# integratedBertha.net
KiCad netlist of a schematic drawn in EAGLE
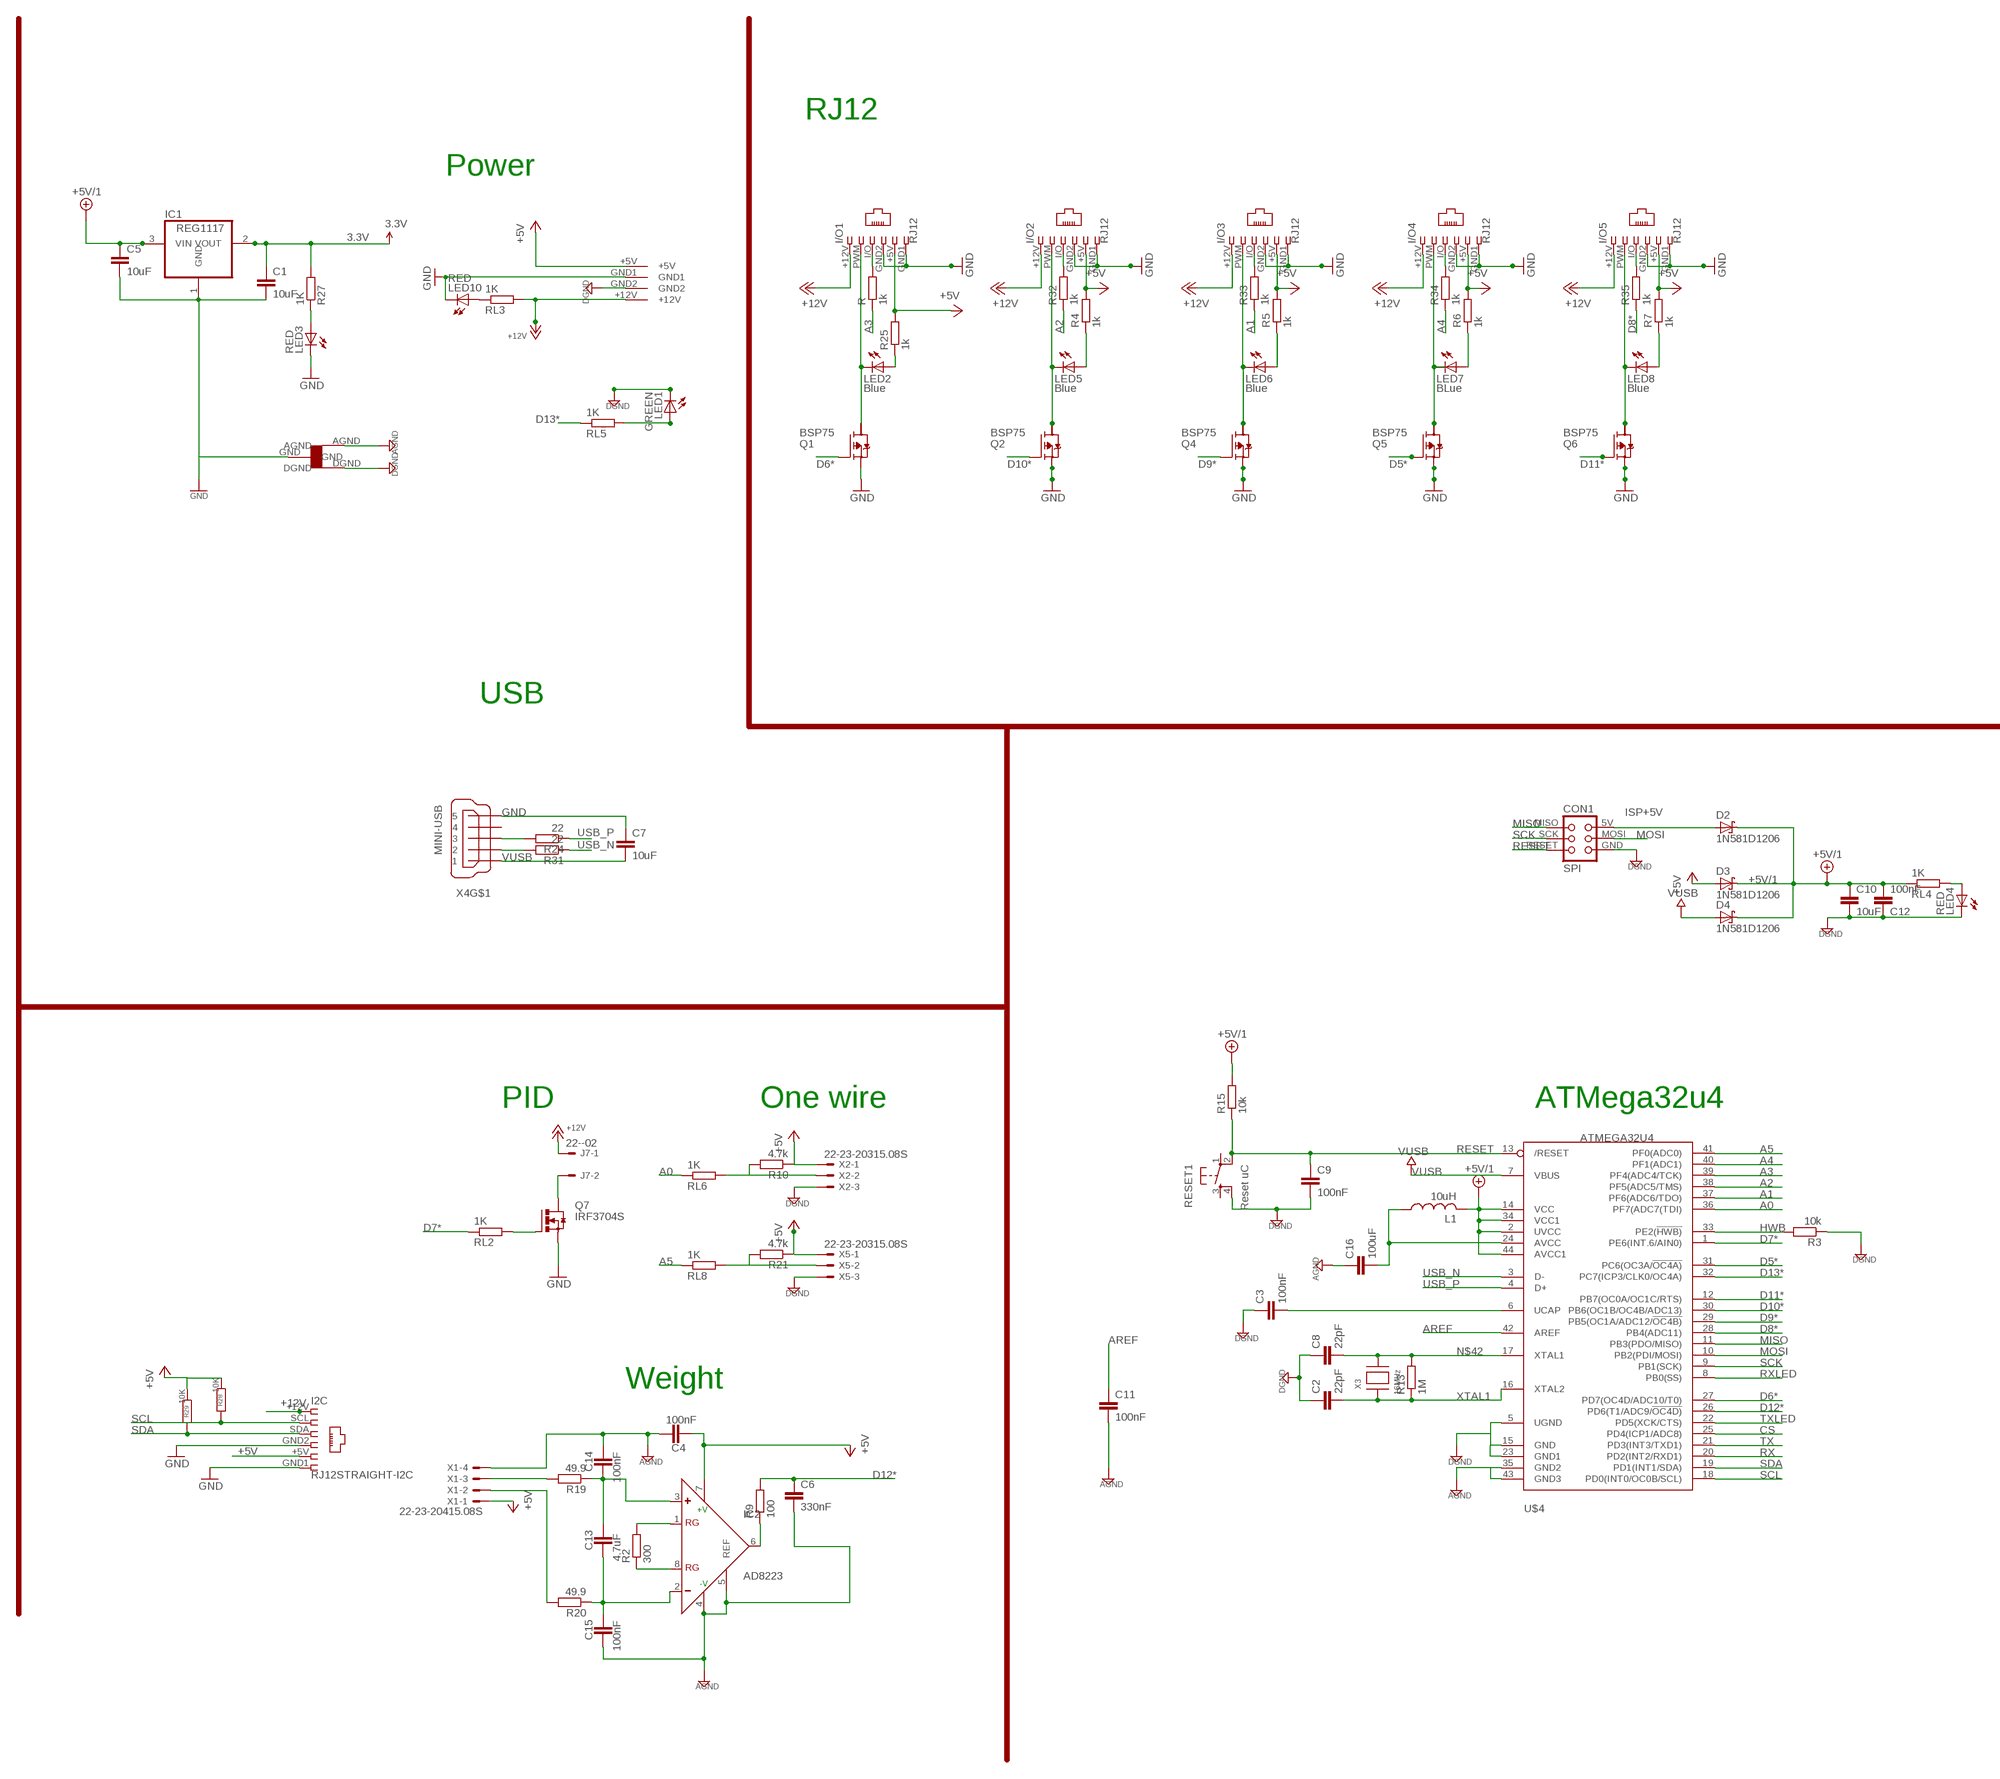
[diagram p0: schematic, sheet 1, part 1 of 2]
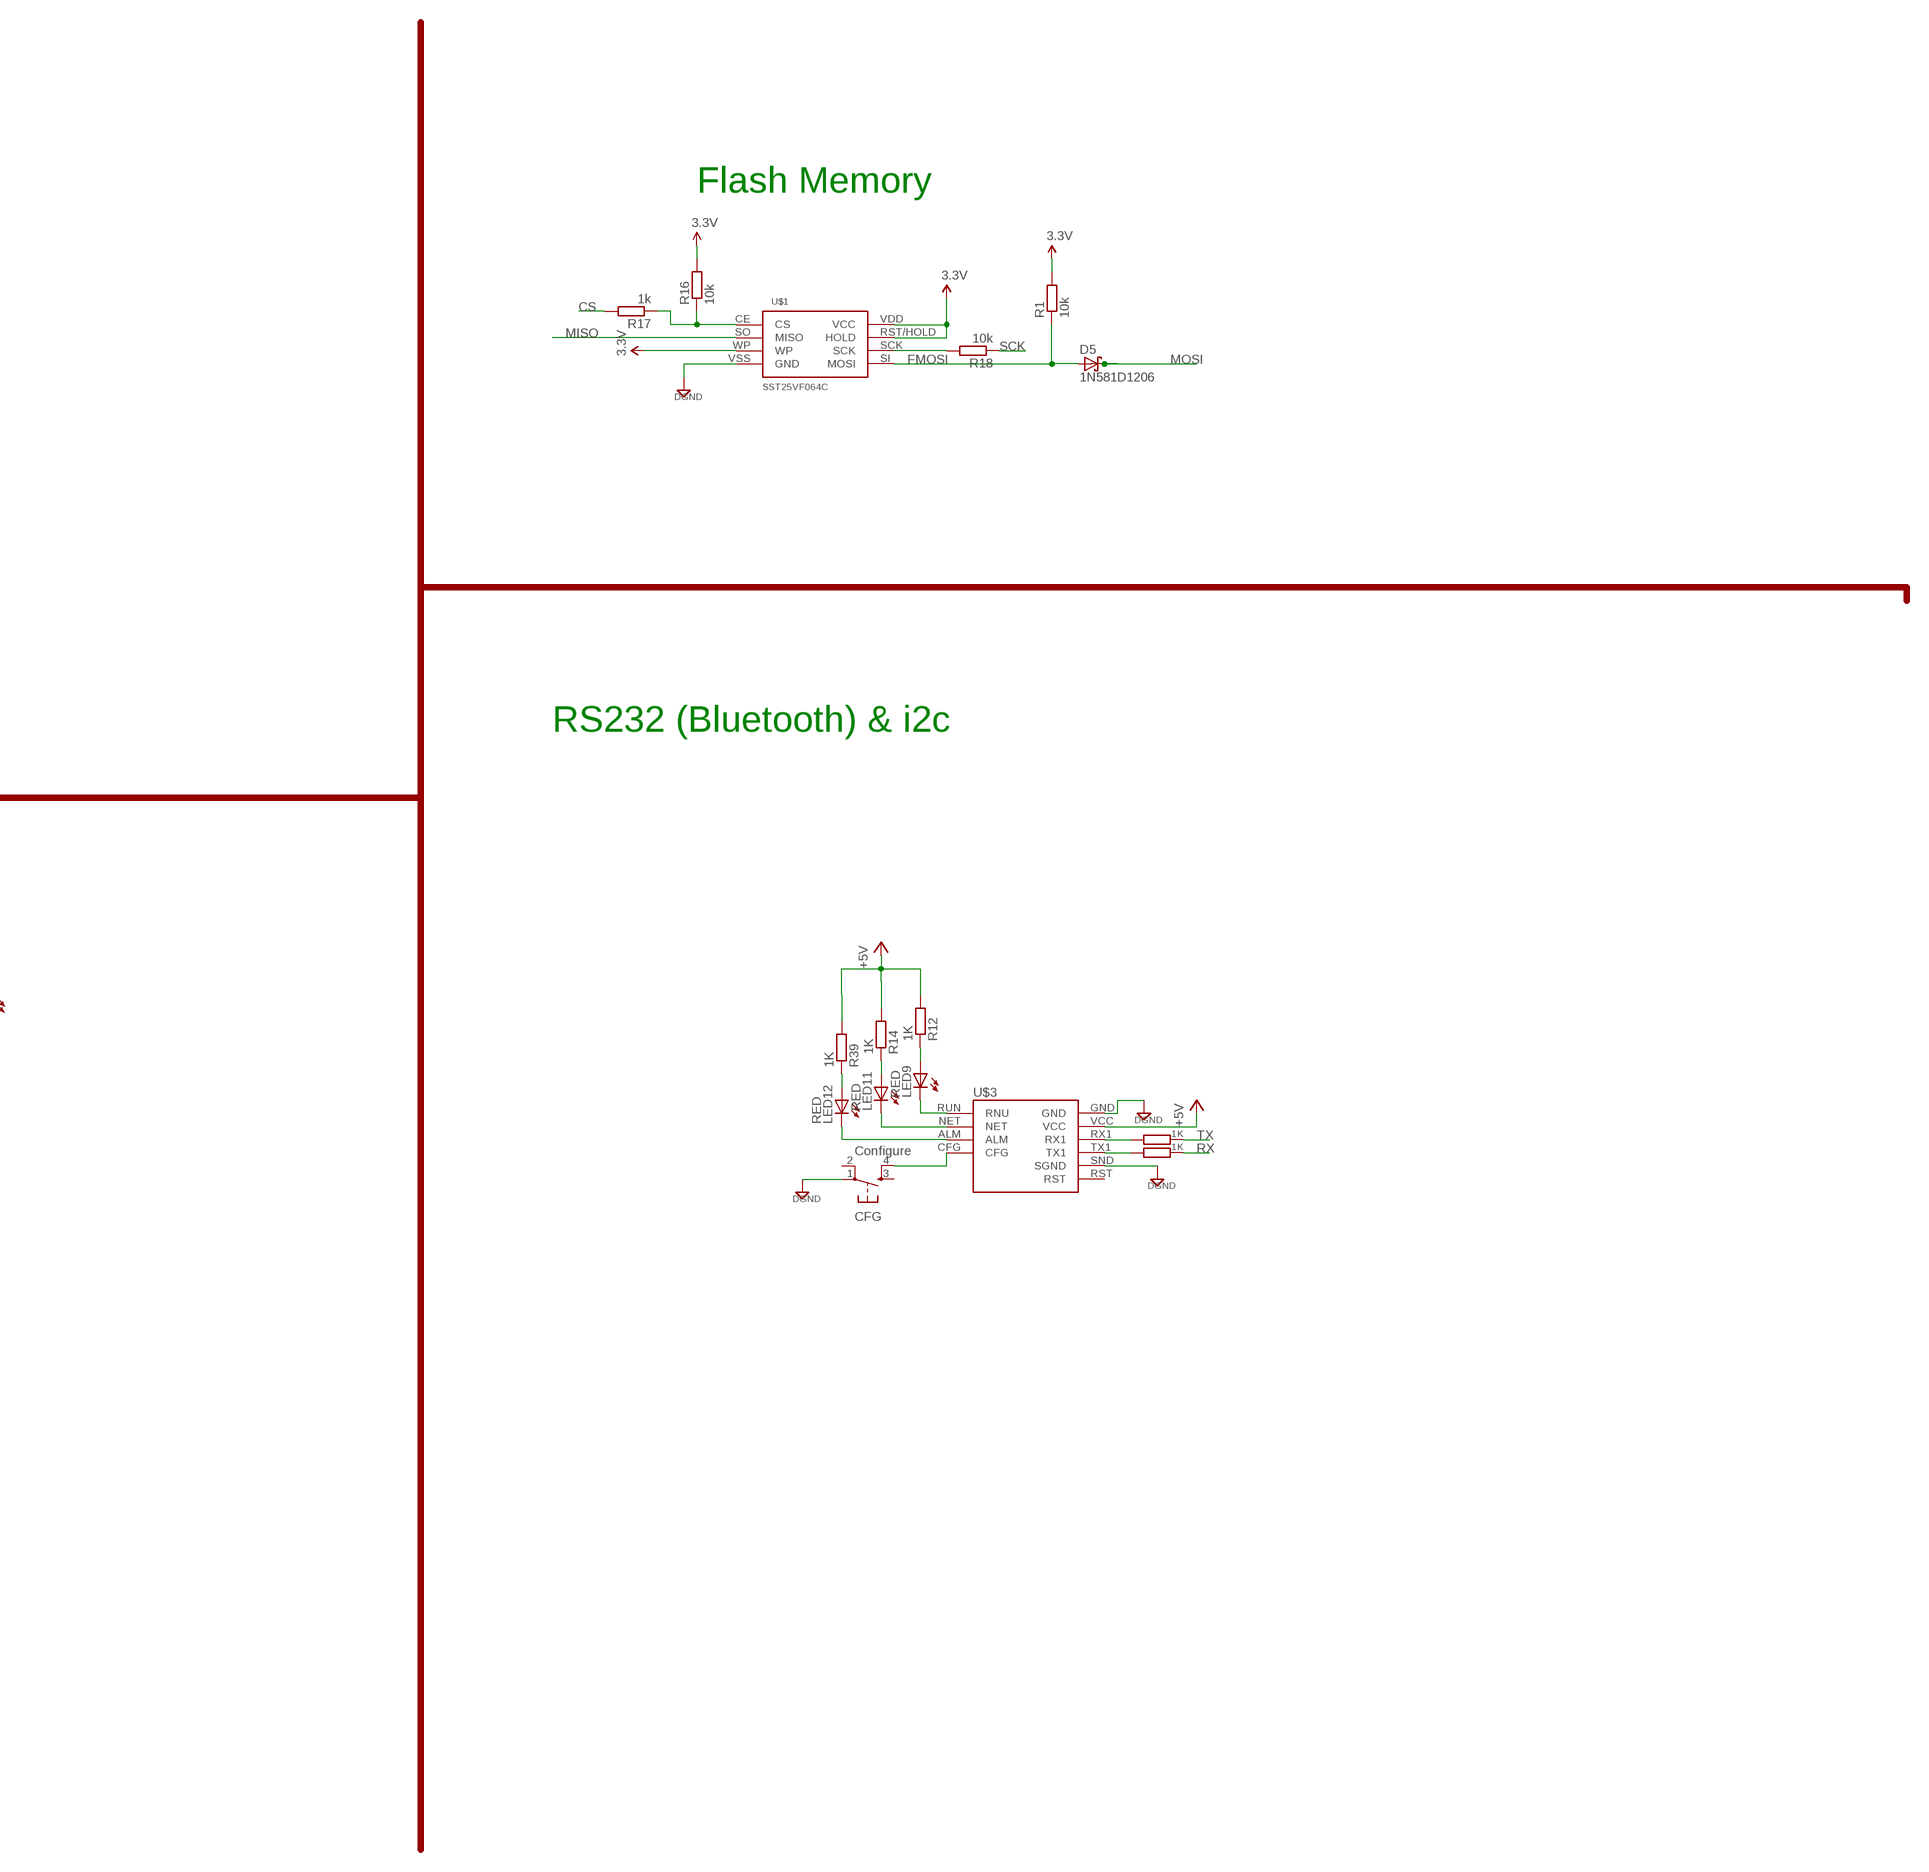
[diagram p1: schematic, sheet 1, part 2 of 2]

(export (version "E")
  (design (tool "Eeschema 10.0.6"))
  (components
    (comp (ref "C1")
      (value "10uF")
      (footprint "eagle-import:C1206")
      (libsource (lib "eagle-import") (part "C-EUC1206"))
    )
    (comp (ref "C2")
      (value "22pF")
      (footprint "eagle-import:C1206")
      (libsource (lib "eagle-import") (part "C-EUC1206"))
    )
    (comp (ref "C3")
      (value "100nF")
      (footprint "eagle-import:C1206")
      (libsource (lib "eagle-import") (part "C-EUC1206"))
    )
    (comp (ref "C4")
      (value "100nF")
      (footprint "eagle-import:C1206")
      (libsource (lib "eagle-import") (part "C-EUC1206"))
    )
    (comp (ref "C5")
      (value "10uF")
      (footprint "eagle-import:C1206")
      (libsource (lib "eagle-import") (part "C-EUC1206"))
    )
    (comp (ref "C6")
      (value "330nF")
      (footprint "eagle-import:C1206")
      (libsource (lib "eagle-import") (part "C-EUC1206"))
    )
    (comp (ref "C7")
      (value "10uF")
      (footprint "eagle-import:C1206")
      (libsource (lib "eagle-import") (part "C-EUC1206"))
    )
    (comp (ref "C8")
      (value "22pF")
      (footprint "eagle-import:C1206")
      (libsource (lib "eagle-import") (part "C-EUC1206"))
    )
    (comp (ref "C9")
      (value "100nF")
      (footprint "eagle-import:C1206")
      (libsource (lib "eagle-import") (part "C-EUC1206"))
    )
    (comp (ref "C10")
      (value "10uF")
      (footprint "eagle-import:C1206")
      (libsource (lib "eagle-import") (part "C-EUC1206"))
    )
    (comp (ref "C11")
      (value "100nF")
      (footprint "eagle-import:C1206")
      (libsource (lib "eagle-import") (part "C-EUC1206"))
    )
    (comp (ref "C12")
      (value "100nF")
      (footprint "eagle-import:C1206")
      (libsource (lib "eagle-import") (part "C-EUC1206"))
    )
    (comp (ref "C13")
      (value "4.7uF")
      (footprint "eagle-import:C1206")
      (libsource (lib "eagle-import") (part "C-EUC1206"))
    )
    (comp (ref "C14")
      (value "100nF")
      (footprint "eagle-import:C1206")
      (libsource (lib "eagle-import") (part "C-EUC1206"))
    )
    (comp (ref "C15")
      (value "100nF")
      (footprint "eagle-import:C1206")
      (libsource (lib "eagle-import") (part "C-EUC1206"))
    )
    (comp (ref "C16")
      (value "100uF")
      (footprint "eagle-import:C1206")
      (libsource (lib "eagle-import") (part "C-EUC1206"))
    )
    (comp (ref "CFG")
      (value "Configure")
      (footprint "eagle-import:TACTILE_SWITCH_SMD")
      (libsource (lib "eagle-import") (part "TAC_SWITCHSMD"))
    )
    (comp (ref "CON1")
      (value "SPI")
      (footprint "eagle-import:TC2030-MCP-NL")
      (libsource (lib "eagle-import") (part "TINYISPT"))
    )
    (comp (ref "D2")
      (value "1N581D1206")
      (footprint "eagle-import:LED-1206")
      (libsource (lib "eagle-import") (part "1N581D1206"))
    )
    (comp (ref "D3")
      (value "1N581D1206")
      (footprint "eagle-import:LED-1206")
      (libsource (lib "eagle-import") (part "1N581D1206"))
    )
    (comp (ref "D4")
      (value "1N581D1206")
      (footprint "eagle-import:LED-1206")
      (libsource (lib "eagle-import") (part "1N581D1206"))
    )
    (comp (ref "D5")
      (value "1N581D1206")
      (footprint "eagle-import:LED-1206")
      (libsource (lib "eagle-import") (part "1N581D1206"))
    )
    (comp (ref "I/O1")
      (value "RJ12")
      (footprint "eagle-import:RJ12-STRAIGHT")
      (libsource (lib "eagle-import") (part "RJ12STRAIGHT"))
    )
    (comp (ref "I/O2")
      (value "RJ12")
      (footprint "eagle-import:RJ12-STRAIGHT")
      (libsource (lib "eagle-import") (part "RJ12STRAIGHT"))
    )
    (comp (ref "I/O3")
      (value "RJ12")
      (footprint "eagle-import:RJ12-STRAIGHT")
      (libsource (lib "eagle-import") (part "RJ12STRAIGHT"))
    )
    (comp (ref "I/O4")
      (value "RJ12")
      (footprint "eagle-import:RJ12-STRAIGHT")
      (libsource (lib "eagle-import") (part "RJ12STRAIGHT"))
    )
    (comp (ref "I/O5")
      (value "RJ12")
      (footprint "eagle-import:RJ12-STRAIGHT")
      (libsource (lib "eagle-import") (part "RJ12STRAIGHT"))
    )
    (comp (ref "I2C")
      (value "RJ12STRAIGHT-I2C")
      (footprint "eagle-import:RJ12-STRAIGHT-I2C")
      (libsource (lib "eagle-import") (part "RJ12STRAIGHT-I2C"))
    )
    (comp (ref "IC1")
      (value "REG1117")
      (footprint "eagle-import:SOT223")
      (libsource (lib "eagle-import") (part "REG1117"))
    )
    (comp (ref "IC2")
      (value "AD8223")
      (footprint "eagle-import:SO8")
      (fields (field (name "MPN") "AD620AR"))
      (libsource (lib "eagle-import") (part "AD620R"))
    )
    (comp (ref "J7")
      (value "22--02")
      (footprint "eagle-import:2-PIN-5.08S")
      (libsource (lib "eagle-import") (part "22-?-02"))
    )
    (comp (ref "L1")
      (value "10uH")
      (footprint "eagle-import:L2012C")
      (libsource (lib "eagle-import") (part "L-USL2012C"))
    )
    (comp (ref "LED1")
      (value "GREEN")
      (footprint "eagle-import:CHIPLED_1206")
      (libsource (lib "eagle-import") (part "LEDCHIPLED_1206"))
    )
    (comp (ref "LED2")
      (value "Blue")
      (footprint "eagle-import:CHIPLED_1206")
      (libsource (lib "eagle-import") (part "LEDCHIPLED_1206"))
    )
    (comp (ref "LED3")
      (value "RED")
      (footprint "eagle-import:CHIPLED_1206")
      (libsource (lib "eagle-import") (part "LEDCHIPLED_1206"))
    )
    (comp (ref "LED4")
      (value "RED")
      (footprint "eagle-import:CHIPLED_1206")
      (libsource (lib "eagle-import") (part "LEDCHIPLED_1206"))
    )
    (comp (ref "LED5")
      (value "Blue")
      (footprint "eagle-import:CHIPLED_1206")
      (libsource (lib "eagle-import") (part "LEDCHIPLED_1206"))
    )
    (comp (ref "LED6")
      (value "Blue")
      (footprint "eagle-import:CHIPLED_1206")
      (libsource (lib "eagle-import") (part "LEDCHIPLED_1206"))
    )
    (comp (ref "LED7")
      (value "BLue")
      (footprint "eagle-import:CHIPLED_1206")
      (libsource (lib "eagle-import") (part "LEDCHIPLED_1206"))
    )
    (comp (ref "LED8")
      (value "Blue")
      (footprint "eagle-import:CHIPLED_1206")
      (libsource (lib "eagle-import") (part "LEDCHIPLED_1206"))
    )
    (comp (ref "LED9")
      (value "RED")
      (footprint "eagle-import:CHIPLED_1206")
      (libsource (lib "eagle-import") (part "LEDCHIPLED_1206"))
    )
    (comp (ref "LED10")
      (value "RED")
      (footprint "eagle-import:CHIPLED_1206")
      (libsource (lib "eagle-import") (part "LEDCHIPLED_1206"))
    )
    (comp (ref "LED11")
      (value "RED")
      (footprint "eagle-import:CHIPLED_1206")
      (libsource (lib "eagle-import") (part "LEDCHIPLED_1206"))
    )
    (comp (ref "LED12")
      (value "RED")
      (footprint "eagle-import:CHIPLED_1206")
      (libsource (lib "eagle-import") (part "LEDCHIPLED_1206"))
    )
    (comp (ref "Q1")
      (value "BSP75")
      (footprint "eagle-import:PG-SOT-223")
      (libsource (lib "eagle-import") (part "BSP613P"))
    )
    (comp (ref "Q2")
      (value "BSP75")
      (footprint "eagle-import:PG-SOT-223")
      (libsource (lib "eagle-import") (part "BSP613P"))
    )
    (comp (ref "Q4")
      (value "BSP75")
      (footprint "eagle-import:PG-SOT-223")
      (libsource (lib "eagle-import") (part "BSP613P"))
    )
    (comp (ref "Q5")
      (value "BSP75")
      (footprint "eagle-import:PG-SOT-223")
      (libsource (lib "eagle-import") (part "BSP613P"))
    )
    (comp (ref "Q6")
      (value "BSP75")
      (footprint "eagle-import:PG-SOT-223")
      (libsource (lib "eagle-import") (part "BSP613P"))
    )
    (comp (ref "Q7")
      (value "IRF3704S")
      (footprint "eagle-import:D2PACK")
      (libsource (lib "eagle-import") (part "IRF3704S"))
    )
    (comp (ref "R")
      (value "1k")
      (footprint "eagle-import:R0805")
      (libsource (lib "eagle-import") (part "R-EU_R0805"))
    )
    (comp (ref "R1")
      (value "10k")
      (footprint "eagle-import:R0805")
      (libsource (lib "eagle-import") (part "R-EU_R0805"))
    )
    (comp (ref "R2")
      (value "300")
      (footprint "eagle-import:R1206")
      (libsource (lib "eagle-import") (part "resistor_R-EU_R1206"))
    )
    (comp (ref "R3")
      (value "10k")
      (footprint "eagle-import:M0805")
      (libsource (lib "eagle-import") (part "resistor_R-EU_M0805"))
    )
    (comp (ref "R4")
      (value "1k")
      (footprint "eagle-import:R0805")
      (libsource (lib "eagle-import") (part "R-EU_R0805"))
    )
    (comp (ref "R5")
      (value "1k")
      (footprint "eagle-import:R0805")
      (libsource (lib "eagle-import") (part "R-EU_R0805"))
    )
    (comp (ref "R6")
      (value "1k")
      (footprint "eagle-import:R0805")
      (libsource (lib "eagle-import") (part "R-EU_R0805"))
    )
    (comp (ref "R7")
      (value "1k")
      (footprint "eagle-import:R0805")
      (libsource (lib "eagle-import") (part "R-EU_R0805"))
    )
    (comp (ref "R8")
      (value "1K")
      (footprint "eagle-import:R0805")
      (libsource (lib "eagle-import") (part "R-EU_R0805"))
    )
    (comp (ref "R9")
      (value "100")
      (footprint "eagle-import:R1206")
      (libsource (lib "eagle-import") (part "resistor_R-EU_R1206"))
    )
    (comp (ref "R10")
      (value "4.7k")
      (footprint "eagle-import:R1206")
      (libsource (lib "eagle-import") (part "resistor_R-EU_R1206"))
    )
    (comp (ref "R11")
      (value "1K")
      (footprint "eagle-import:R0805")
      (libsource (lib "eagle-import") (part "R-EU_R0805"))
    )
    (comp (ref "R12")
      (value "1K")
      (footprint "eagle-import:R0805")
      (libsource (lib "eagle-import") (part "R-EU_R0805"))
    )
    (comp (ref "R13")
      (value "1M")
      (footprint "eagle-import:R1206")
      (libsource (lib "eagle-import") (part "R-EU_R1206"))
    )
    (comp (ref "R14")
      (value "1K")
      (footprint "eagle-import:R0805")
      (libsource (lib "eagle-import") (part "R-EU_R0805"))
    )
    (comp (ref "R15")
      (value "10k")
      (footprint "eagle-import:M0805")
      (libsource (lib "eagle-import") (part "resistor_R-EU_M0805"))
    )
    (comp (ref "R16")
      (value "10k")
      (footprint "eagle-import:R0805")
      (libsource (lib "eagle-import") (part "R-EU_R0805"))
    )
    (comp (ref "R17")
      (value "1k")
      (footprint "eagle-import:R0805")
      (libsource (lib "eagle-import") (part "R-EU_R0805"))
    )
    (comp (ref "R18")
      (value "10k")
      (footprint "eagle-import:R0805")
      (libsource (lib "eagle-import") (part "R-EU_R0805"))
    )
    (comp (ref "R19")
      (value "49.9")
      (footprint "eagle-import:R1206")
      (libsource (lib "eagle-import") (part "resistor_R-EU_R1206"))
    )
    (comp (ref "R20")
      (value "49.9")
      (footprint "eagle-import:R1206")
      (libsource (lib "eagle-import") (part "resistor_R-EU_R1206"))
    )
    (comp (ref "R21")
      (value "4.7k")
      (footprint "eagle-import:R1206")
      (libsource (lib "eagle-import") (part "resistor_R-EU_R1206"))
    )
    (comp (ref "R24")
      (value "22")
      (footprint "eagle-import:M1206")
      (libsource (lib "eagle-import") (part "resistor_R-EU_M1206"))
    )
    (comp (ref "R25")
      (value "1k")
      (footprint "eagle-import:R0805")
      (libsource (lib "eagle-import") (part "R-EU_R0805"))
    )
    (comp (ref "R27")
      (value "1K")
      (footprint "eagle-import:R0805")
      (libsource (lib "eagle-import") (part "R-EU_R0805"))
    )
    (comp (ref "R28")
      (value "10K")
      (footprint "eagle-import:M0805")
      (libsource (lib "eagle-import") (part "resistor_R-EU_M0805"))
    )
    (comp (ref "R29")
      (value "10K")
      (footprint "eagle-import:M0805")
      (libsource (lib "eagle-import") (part "resistor_R-EU_M0805"))
    )
    (comp (ref "R31")
      (value "22")
      (footprint "eagle-import:M1206")
      (libsource (lib "eagle-import") (part "resistor_R-EU_M1206"))
    )
    (comp (ref "R32")
      (value "1k")
      (footprint "eagle-import:R0805")
      (libsource (lib "eagle-import") (part "R-EU_R0805"))
    )
    (comp (ref "R33")
      (value "1k")
      (footprint "eagle-import:R0805")
      (libsource (lib "eagle-import") (part "R-EU_R0805"))
    )
    (comp (ref "R34")
      (value "1k")
      (footprint "eagle-import:R0805")
      (libsource (lib "eagle-import") (part "R-EU_R0805"))
    )
    (comp (ref "R35")
      (value "1k")
      (footprint "eagle-import:R0805")
      (libsource (lib "eagle-import") (part "R-EU_R0805"))
    )
    (comp (ref "R39")
      (value "1K")
      (footprint "eagle-import:R0805")
      (libsource (lib "eagle-import") (part "R-EU_R0805"))
    )
    (comp (ref "RESET1")
      (value "Reset uC")
      (footprint "eagle-import:TACTILE_SWITCH_SMD")
      (libsource (lib "eagle-import") (part "TAC_SWITCHSMD"))
    )
    (comp (ref "RL2")
      (value "1K")
      (footprint "eagle-import:R0805")
      (libsource (lib "eagle-import") (part "R-EU_R0805"))
    )
    (comp (ref "RL3")
      (value "1K")
      (footprint "eagle-import:R0805")
      (libsource (lib "eagle-import") (part "R-EU_R0805"))
    )
    (comp (ref "RL4")
      (value "1K")
      (footprint "eagle-import:R0805")
      (libsource (lib "eagle-import") (part "resistor_R-EU_R0805"))
    )
    (comp (ref "RL5")
      (value "1K")
      (footprint "eagle-import:R0805")
      (libsource (lib "eagle-import") (part "R-EU_R0805"))
    )
    (comp (ref "RL6")
      (value "1K")
      (footprint "eagle-import:R0805")
      (libsource (lib "eagle-import") (part "R-EU_R0805"))
    )
    (comp (ref "RL8")
      (value "1K")
      (footprint "eagle-import:R0805")
      (libsource (lib "eagle-import") (part "R-EU_R0805"))
    )
    (comp (ref "U$1")
      (value "SST25VF064C")
      (footprint "eagle-import:SOIC_8-LEAD")
      (libsource (lib "eagle-import") (part "SST25VF064C"))
    )
    (comp (ref "U$2")
      (value "STARGND")
      (footprint "eagle-import:STAR")
      (libsource (lib "eagle-import") (part "STARGND"))
    )
    (comp (ref "U$3")
      (value "SZ05-ZIGBEETHROUGHHOLE")
      (footprint "eagle-import:SZ05-ZIGBEE4")
      (libsource (lib "eagle-import") (part "SZ05-ZIGBEETHROUGHHOLE"))
    )
    (comp (ref "U$4")
      (value "ATMEGA32U4")
      (footprint "eagle-import:TQFP44")
      (libsource (lib "eagle-import") (part "ATMEGA32U4-AU"))
    )
    (comp (ref "U$6")
      (value "KPJX-4S-S")
      (footprint "eagle-import:KPJX-4S-S")
      (libsource (lib "eagle-import") (part "KPJX-4S-S"))
    )
    (comp (ref "X1")
      (value "22-23-20415.08S")
      (footprint "eagle-import:4-PIN-5.08S")
      (libsource (lib "eagle-import") (part "22-23-20415.08S"))
    )
    (comp (ref "X2")
      (value "22-23-20315.08S")
      (footprint "eagle-import:3-PIN-5.08S")
      (libsource (lib "eagle-import") (part "22-23-20315.08S"))
    )
    (comp (ref "X3")
      (value "16MHz")
      (footprint "eagle-import:NX6035")
      (libsource (lib "eagle-import") (part "XTALNX6035"))
    )
    (comp (ref "X4")
      (value "MINI-USB")
      (footprint "eagle-import:32005-201")
      (libsource (lib "eagle-import") (part "MINI-USB-SCHIELD-32005-201"))
    )
    (comp (ref "X5")
      (value "22-23-20315.08S")
      (footprint "eagle-import:3-PIN-5.08S")
      (libsource (lib "eagle-import") (part "22-23-20315.08S"))
    )
  )
  (nets
    (net (code "1") (name "+5V") (class "Default")
      (node (ref "C4") (pin "2") (pinfunction "2_2") (pintype "passive"))
      (node (ref "D3") (pin "A") (pinfunction "A_A") (pintype "passive"))
      (node (ref "I/O1") (pin "+5V") (pinfunction "5_+5V") (pintype "bidirectional"))
      (node (ref "I/O2") (pin "+5V") (pinfunction "5_+5V") (pintype "bidirectional"))
      (node (ref "I/O3") (pin "+5V") (pinfunction "5_+5V") (pintype "bidirectional"))
      (node (ref "I/O4") (pin "+5V") (pinfunction "5_+5V") (pintype "bidirectional"))
      (node (ref "I/O5") (pin "+5V") (pinfunction "5_+5V") (pintype "bidirectional"))
      (node (ref "I2C") (pin "+5V") (pinfunction "5_+5V") (pintype "bidirectional"))
      (node (ref "IC2") (pin "7") (pinfunction "+V_7") (pintype "power_in"))
      (node (ref "R10") (pin "1") (pinfunction "1_1") (pintype "passive"))
      (node (ref "R12") (pin "2") (pinfunction "2_2") (pintype "passive"))
      (node (ref "R14") (pin "2") (pinfunction "2_2") (pintype "passive"))
      (node (ref "R21") (pin "1") (pinfunction "1_1") (pintype "passive"))
      (node (ref "R25") (pin "2") (pinfunction "2_2") (pintype "passive"))
      (node (ref "R28") (pin "1") (pinfunction "1_1") (pintype "passive"))
      (node (ref "R29") (pin "1") (pinfunction "1_1") (pintype "passive"))
      (node (ref "R39") (pin "2") (pinfunction "2_2") (pintype "passive"))
      (node (ref "R4") (pin "2") (pinfunction "2_2") (pintype "passive"))
      (node (ref "R5") (pin "2") (pinfunction "2_2") (pintype "passive"))
      (node (ref "R6") (pin "2") (pinfunction "2_2") (pintype "passive"))
      (node (ref "R7") (pin "2") (pinfunction "2_2") (pintype "passive"))
      (node (ref "U$3") (pin "VCC") (pinfunction "VCC_VCC") (pintype "bidirectional"))
      (node (ref "U$6") (pin "+5V") (pinfunction "+5V_+5V") (pintype "power_in"))
      (node (ref "X1") (pin "1") (pinfunction "S_1") (pintype "passive"))
      (node (ref "X2") (pin "1") (pinfunction "S_1") (pintype "passive"))
      (node (ref "X5") (pin "1") (pinfunction "S_1") (pintype "passive"))
    )
    (net (code "2") (name "+5V{slash}1") (class "Default")
      (node (ref "C10") (pin "1") (pinfunction "1_1") (pintype "passive"))
      (node (ref "C12") (pin "2") (pinfunction "2_2") (pintype "passive"))
      (node (ref "C5") (pin "1") (pinfunction "1_1") (pintype "passive"))
      (node (ref "D2") (pin "C") (pinfunction "C_C") (pintype "passive"))
      (node (ref "D3") (pin "C") (pinfunction "C_C") (pintype "passive"))
      (node (ref "D4") (pin "C") (pinfunction "C_C") (pintype "passive"))
      (node (ref "IC1") (pin "3") (pinfunction "VIN_3") (pintype "input"))
      (node (ref "L1") (pin "2") (pinfunction "2_2") (pintype "passive"))
      (node (ref "R15") (pin "2") (pinfunction "2_2") (pintype "passive"))
      (node (ref "RL4") (pin "1") (pinfunction "1_1") (pintype "passive"))
      (node (ref "U$4") (pin "14") (pinfunction "VCC_14") (pintype "bidirectional"))
      (node (ref "U$4") (pin "2") (pinfunction "UVCC_2") (pintype "bidirectional"))
      (node (ref "U$4") (pin "34") (pinfunction "VCC1_34") (pintype "bidirectional"))
      (node (ref "U$4") (pin "44") (pinfunction "AVCC1_44") (pintype "bidirectional"))
    )
    (net (code "3") (name "+12V") (class "Default")
      (node (ref "I/O1") (pin "+12V") (pinfunction "1_+12V") (pintype "bidirectional"))
      (node (ref "I/O2") (pin "+12V") (pinfunction "1_+12V") (pintype "bidirectional"))
      (node (ref "I/O3") (pin "+12V") (pinfunction "1_+12V") (pintype "bidirectional"))
      (node (ref "I/O4") (pin "+12V") (pinfunction "1_+12V") (pintype "bidirectional"))
      (node (ref "I/O5") (pin "+12V") (pinfunction "1_+12V") (pintype "bidirectional"))
      (node (ref "I2C") (pin "+12V") (pinfunction "1_+12V") (pintype "bidirectional"))
      (node (ref "J7") (pin "1") (pinfunction "S_1") (pintype "passive"))
      (node (ref "RL3") (pin "2") (pinfunction "2_2") (pintype "passive"))
      (node (ref "U$6") (pin "+12V") (pinfunction "+12V_+12V") (pintype "power_in"))
    )
    (net (code "4") (name "/A0") (class "Default")
      (node (ref "RL6") (pin "1") (pinfunction "1_1") (pintype "passive"))
      (node (ref "U$4") (pin "36") (pinfunction "PF7(ADC7(TDI)_36") (pintype "bidirectional"))
    )
    (net (code "5") (name "/A1") (class "Default")
      (node (ref "R33") (pin "1") (pinfunction "1_1") (pintype "passive"))
      (node (ref "U$4") (pin "37") (pinfunction "PF6(ADC6/TDO)_37") (pintype "bidirectional"))
    )
    (net (code "6") (name "/A2") (class "Default")
      (node (ref "R32") (pin "1") (pinfunction "1_1") (pintype "passive"))
      (node (ref "U$4") (pin "38") (pinfunction "PF5(ADC5/TMS)_38") (pintype "bidirectional"))
    )
    (net (code "7") (name "/A3") (class "Default")
      (node (ref "R") (pin "1") (pinfunction "1_1") (pintype "passive"))
      (node (ref "U$4") (pin "39") (pinfunction "PF4(ADC4/TCK)_39") (pintype "bidirectional"))
    )
    (net (code "8") (name "/A4") (class "Default")
      (node (ref "R34") (pin "1") (pinfunction "1_1") (pintype "passive"))
      (node (ref "U$4") (pin "40") (pinfunction "PF1(ADC1)_40") (pintype "bidirectional"))
    )
    (net (code "9") (name "/A5") (class "Default")
      (node (ref "RL8") (pin "1") (pinfunction "1_1") (pintype "passive"))
      (node (ref "U$4") (pin "41") (pinfunction "PF0(ADC0)_41") (pintype "bidirectional"))
    )
    (net (code "10") (name "/AREF") (class "Default")
      (node (ref "C11") (pin "1") (pinfunction "1_1") (pintype "passive"))
      (node (ref "U$4") (pin "42") (pinfunction "AREF_42") (pintype "bidirectional"))
    )
    (net (code "11") (name "/CS") (class "Default")
      (node (ref "R17") (pin "2") (pinfunction "2_2") (pintype "passive"))
      (node (ref "U$4") (pin "25") (pinfunction "PD4(ICP1/ADC8)_25") (pintype "bidirectional"))
    )
    (net (code "12") (name "/D5*") (class "Default")
      (node (ref "Q5") (pin "1") (pinfunction "G_1") (pintype "passive"))
      (node (ref "U$4") (pin "31") (pinfunction "PC6(OC3A/~{OC4A})_31") (pintype "bidirectional"))
    )
    (net (code "13") (name "/D6*") (class "Default")
      (node (ref "Q1") (pin "1") (pinfunction "G_1") (pintype "passive"))
      (node (ref "U$4") (pin "27") (pinfunction "PD7(OC4D/ADC10/T0)_27") (pintype "bidirectional"))
    )
    (net (code "14") (name "/D7*") (class "Default")
      (node (ref "RL2") (pin "1") (pinfunction "1_1") (pintype "passive"))
      (node (ref "U$4") (pin "1") (pinfunction "PE6(INT.6/AIN0)_1") (pintype "bidirectional"))
    )
    (net (code "15") (name "/D8*") (class "Default")
      (node (ref "R35") (pin "1") (pinfunction "1_1") (pintype "passive"))
      (node (ref "U$4") (pin "28") (pinfunction "PB4(ADC11)_28") (pintype "bidirectional"))
    )
    (net (code "16") (name "/D9*") (class "Default")
      (node (ref "Q4") (pin "1") (pinfunction "G_1") (pintype "passive"))
      (node (ref "U$4") (pin "29") (pinfunction "PB5(OC1A/ADC12/~{OC4B})_29") (pintype "bidirectional"))
    )
    (net (code "17") (name "/D10*") (class "Default")
      (node (ref "Q2") (pin "1") (pinfunction "G_1") (pintype "passive"))
      (node (ref "U$4") (pin "30") (pinfunction "PB6(OC1B/OC4B/ADC13)_30") (pintype "bidirectional"))
    )
    (net (code "18") (name "/D11*") (class "Default")
      (node (ref "Q6") (pin "1") (pinfunction "G_1") (pintype "passive"))
      (node (ref "U$4") (pin "12") (pinfunction "PB7(OC0A/OC1C/RTS)_12") (pintype "bidirectional"))
    )
    (net (code "19") (name "/D12*") (class "Default")
      (node (ref "C6") (pin "1") (pinfunction "1_1") (pintype "passive"))
      (node (ref "R9") (pin "2") (pinfunction "2_2") (pintype "passive"))
      (node (ref "U$4") (pin "26") (pinfunction "PD6(T1/ADC9/~{OC4D})_26") (pintype "bidirectional"))
    )
    (net (code "20") (name "/D13*") (class "Default")
      (node (ref "RL5") (pin "1") (pinfunction "1_1") (pintype "passive"))
      (node (ref "U$4") (pin "32") (pinfunction "PC7(ICP3/CLK0/OC4A)_32") (pintype "bidirectional"))
    )
    (net (code "21") (name "/FMOSI") (class "Default")
      (node (ref "D5") (pin "A") (pinfunction "A_A") (pintype "passive"))
      (node (ref "R1") (pin "1") (pinfunction "1_1") (pintype "passive"))
      (node (ref "U$1") (pin "SI") (pinfunction "MOSI_SI") (pintype "bidirectional"))
    )
    (net (code "22") (name "/HWB") (class "Default")
      (node (ref "R3") (pin "2") (pinfunction "2_2") (pintype "passive"))
      (node (ref "U$4") (pin "33") (pinfunction "PE2(~{HWB})_33") (pintype "bidirectional"))
    )
    (net (code "23") (name "/ISP+5V") (class "Default")
      (node (ref "CON1") (pin "5V") (pinfunction "VCC_5V") (pintype "passive"))
      (node (ref "D2") (pin "A") (pinfunction "A_A") (pintype "passive"))
    )
    (net (code "24") (name "/MISO") (class "Default")
      (node (ref "CON1") (pin "MISO") (pinfunction "MISO_MISO") (pintype "passive"))
      (node (ref "U$1") (pin "SO") (pinfunction "MISO_SO") (pintype "bidirectional"))
      (node (ref "U$4") (pin "11") (pinfunction "PB3(PDO/MISO)_11") (pintype "bidirectional"))
    )
    (net (code "25") (name "/MOSI") (class "Default")
      (node (ref "CON1") (pin "MOSI") (pinfunction "MOSI_MOSI") (pintype "passive"))
      (node (ref "D5") (pin "C") (pinfunction "C_C") (pintype "passive"))
      (node (ref "U$4") (pin "10") (pinfunction "PB2(PDI/MOSI)_10") (pintype "bidirectional"))
    )
    (net (code "26") (name "/N$42") (class "Default")
      (node (ref "C8") (pin "2") (pinfunction "2_2") (pintype "passive"))
      (node (ref "R13") (pin "2") (pinfunction "2_2") (pintype "passive"))
      (node (ref "U$4") (pin "17") (pinfunction "XTAL1_17") (pintype "bidirectional"))
      (node (ref "X3") (pin "P$2") (pinfunction "P$2_P$2") (pintype "bidirectional"))
    )
    (net (code "27") (name "/RESET") (class "Default")
      (node (ref "C9") (pin "1") (pinfunction "1_1") (pintype "passive"))
      (node (ref "CON1") (pin "RESET") (pinfunction "RESET_RESET") (pintype "passive"))
      (node (ref "R15") (pin "1") (pinfunction "1_1") (pintype "passive"))
      (node (ref "RESET1") (pin "2") (pinfunction "2_2") (pintype "passive"))
      (node (ref "U$4") (pin "13") (pinfunction "/RESET_13") (pintype "bidirectional"))
    )
    (net (code "28") (name "/RX") (class "Default")
      (node (ref "R8") (pin "1") (pinfunction "1_1") (pintype "passive"))
      (node (ref "U$4") (pin "20") (pinfunction "PD2(INT2/RXD1)_20") (pintype "bidirectional"))
    )
    (net (code "29") (name "/RXLED") (class "Default")
      (node (ref "U$4") (pin "8") (pinfunction "PB0(SS)_8") (pintype "bidirectional"))
    )
    (net (code "30") (name "/SCK") (class "Default")
      (node (ref "CON1") (pin "SCK") (pinfunction "SCK_SCK") (pintype "passive"))
      (node (ref "R18") (pin "1") (pinfunction "1_1") (pintype "passive"))
      (node (ref "U$4") (pin "9") (pinfunction "PB1(SCK)_9") (pintype "bidirectional"))
    )
    (net (code "31") (name "/SCL") (class "Default")
      (node (ref "I2C") (pin "SCL") (pinfunction "2_SCL") (pintype "bidirectional"))
      (node (ref "R28") (pin "2") (pinfunction "2_2") (pintype "passive"))
      (node (ref "U$4") (pin "18") (pinfunction "PD0(INT0/OC0B/SCL)_18") (pintype "bidirectional"))
    )
    (net (code "32") (name "/SDA") (class "Default")
      (node (ref "I2C") (pin "SDA") (pinfunction "3_SDA") (pintype "bidirectional"))
      (node (ref "R29") (pin "2") (pinfunction "2_2") (pintype "passive"))
      (node (ref "U$4") (pin "19") (pinfunction "PD1(INT1/SDA)_19") (pintype "bidirectional"))
    )
    (net (code "33") (name "/TX") (class "Default")
      (node (ref "R11") (pin "1") (pinfunction "1_1") (pintype "passive"))
      (node (ref "U$4") (pin "21") (pinfunction "PD3(INT3/TXD1)_21") (pintype "bidirectional"))
    )
    (net (code "34") (name "/TXLED") (class "Default")
      (node (ref "U$4") (pin "22") (pinfunction "PD5(XCK/CTS)_22") (pintype "bidirectional"))
    )
    (net (code "35") (name "/USB_N") (class "Default")
      (node (ref "R31") (pin "1") (pinfunction "1_1") (pintype "passive"))
      (node (ref "U$4") (pin "3") (pinfunction "D-_3") (pintype "bidirectional"))
    )
    (net (code "36") (name "/USB_P") (class "Default")
      (node (ref "R24") (pin "1") (pinfunction "1_1") (pintype "passive"))
      (node (ref "U$4") (pin "4") (pinfunction "D+_4") (pintype "bidirectional"))
    )
    (net (code "37") (name "/XTAL1") (class "Default")
      (node (ref "C2") (pin "2") (pinfunction "2_2") (pintype "passive"))
      (node (ref "R13") (pin "1") (pinfunction "1_1") (pintype "passive"))
      (node (ref "U$4") (pin "16") (pinfunction "XTAL2_16") (pintype "bidirectional"))
      (node (ref "X3") (pin "P$1") (pinfunction "P$1_P$1") (pintype "bidirectional"))
    )
    (net (code "38") (name "3.3V") (class "Default")
      (node (ref "C1") (pin "1") (pinfunction "1_1") (pintype "passive"))
      (node (ref "IC1") (pin "2") (pinfunction "VOUT_2") (pintype "output"))
      (node (ref "R1") (pin "2") (pinfunction "2_2") (pintype "passive"))
      (node (ref "R16") (pin "2") (pinfunction "2_2") (pintype "passive"))
      (node (ref "R27") (pin "2") (pinfunction "2_2") (pintype "passive"))
      (node (ref "U$1") (pin "RST/HOLD") (pinfunction "HOLD_RST/HOLD") (pintype "bidirectional"))
      (node (ref "U$1") (pin "VDD") (pinfunction "VCC_VDD") (pintype "bidirectional"))
      (node (ref "U$1") (pin "WP") (pinfunction "WP_WP") (pintype "bidirectional"))
    )
    (net (code "39") (name "AGND") (class "Default")
      (node (ref "C11") (pin "2") (pinfunction "2_2") (pintype "passive"))
      (node (ref "C14") (pin "1") (pinfunction "1_1") (pintype "passive"))
      (node (ref "C15") (pin "2") (pinfunction "2_2") (pintype "passive"))
      (node (ref "C16") (pin "1") (pinfunction "1_1") (pintype "passive"))
      (node (ref "C4") (pin "1") (pinfunction "1_1") (pintype "passive"))
      (node (ref "C6") (pin "2") (pinfunction "2_2") (pintype "passive"))
      (node (ref "IC2") (pin "4") (pinfunction "-V_4") (pintype "power_in"))
      (node (ref "IC2") (pin "5") (pinfunction "REF_5") (pintype "passive"))
      (node (ref "U$2") (pin "AGND") (pinfunction "AGND_AGND") (pintype "output"))
      (node (ref "U$4") (pin "35") (pinfunction "GND2_35") (pintype "bidirectional"))
      (node (ref "U$4") (pin "43") (pinfunction "GND3_43") (pintype "bidirectional"))
      (node (ref "X1") (pin "4") (pinfunction "S_4") (pintype "passive"))
    )
    (net (code "40") (name "DGND") (class "Default")
      (node (ref "C10") (pin "2") (pinfunction "2_2") (pintype "passive"))
      (node (ref "C12") (pin "1") (pinfunction "1_1") (pintype "passive"))
      (node (ref "C2") (pin "1") (pinfunction "1_1") (pintype "passive"))
      (node (ref "C3") (pin "1") (pinfunction "1_1") (pintype "passive"))
      (node (ref "C8") (pin "1") (pinfunction "1_1") (pintype "passive"))
      (node (ref "C9") (pin "2") (pinfunction "2_2") (pintype "passive"))
      (node (ref "CFG") (pin "1") (pinfunction "1_1") (pintype "passive"))
      (node (ref "CON1") (pin "GND") (pinfunction "GND_GND") (pintype "passive"))
      (node (ref "LED1") (pin "C") (pinfunction "C_C") (pintype "passive"))
      (node (ref "LED4") (pin "C") (pinfunction "C_C") (pintype "passive"))
      (node (ref "R3") (pin "1") (pinfunction "1_1") (pintype "passive"))
      (node (ref "RESET1") (pin "4") (pinfunction "4_4") (pintype "passive"))
      (node (ref "U$1") (pin "VSS") (pinfunction "GND_VSS") (pintype "bidirectional"))
      (node (ref "U$2") (pin "DGND") (pinfunction "DGND_DGND") (pintype "output"))
      (node (ref "U$3") (pin "GND") (pinfunction "GND_GND") (pintype "bidirectional"))
      (node (ref "U$3") (pin "SND") (pinfunction "SGND_SND") (pintype "bidirectional"))
      (node (ref "U$4") (pin "15") (pinfunction "GND_15") (pintype "bidirectional"))
      (node (ref "U$4") (pin "23") (pinfunction "GND1_23") (pintype "bidirectional"))
      (node (ref "U$4") (pin "5") (pinfunction "UGND_5") (pintype "bidirectional"))
      (node (ref "U$6") (pin "GND2") (pinfunction "GND2_GND2") (pintype "input"))
      (node (ref "X2") (pin "3") (pinfunction "S_3") (pintype "passive"))
      (node (ref "X5") (pin "3") (pinfunction "S_3") (pintype "passive"))
    )
    (net (code "41") (name "GND") (class "Default")
      (node (ref "C1") (pin "2") (pinfunction "2_2") (pintype "passive"))
      (node (ref "C5") (pin "2") (pinfunction "2_2") (pintype "passive"))
      (node (ref "C7") (pin "1") (pinfunction "1_1") (pintype "passive"))
      (node (ref "I/O1") (pin "GND1") (pinfunction "6_GND1") (pintype "bidirectional"))
      (node (ref "I/O1") (pin "GND2") (pinfunction "4_GND2") (pintype "bidirectional"))
      (node (ref "I/O2") (pin "GND1") (pinfunction "6_GND1") (pintype "bidirectional"))
      (node (ref "I/O2") (pin "GND2") (pinfunction "4_GND2") (pintype "bidirectional"))
      (node (ref "I/O3") (pin "GND1") (pinfunction "6_GND1") (pintype "bidirectional"))
      (node (ref "I/O3") (pin "GND2") (pinfunction "4_GND2") (pintype "bidirectional"))
      (node (ref "I/O4") (pin "GND1") (pinfunction "6_GND1") (pintype "bidirectional"))
      (node (ref "I/O4") (pin "GND2") (pinfunction "4_GND2") (pintype "bidirectional"))
      (node (ref "I/O5") (pin "GND1") (pinfunction "6_GND1") (pintype "bidirectional"))
      (node (ref "I/O5") (pin "GND2") (pinfunction "4_GND2") (pintype "bidirectional"))
      (node (ref "I2C") (pin "GND1") (pinfunction "6_GND1") (pintype "bidirectional"))
      (node (ref "I2C") (pin "GND2") (pinfunction "4_GND2") (pintype "bidirectional"))
      (node (ref "IC1") (pin "1") (pinfunction "GND_1") (pintype "power_in"))
      (node (ref "LED10") (pin "C") (pinfunction "C_C") (pintype "passive"))
      (node (ref "LED3") (pin "C") (pinfunction "C_C") (pintype "passive"))
      (node (ref "Q1") (pin "3") (pinfunction "S_3") (pintype "passive"))
      (node (ref "Q2") (pin "3") (pinfunction "S_3") (pintype "passive"))
      (node (ref "Q4") (pin "3") (pinfunction "S_3") (pintype "passive"))
      (node (ref "Q5") (pin "3") (pinfunction "S_3") (pintype "passive"))
      (node (ref "Q6") (pin "3") (pinfunction "S_3") (pintype "passive"))
      (node (ref "Q7") (pin "3") (pinfunction "S_3") (pintype "passive"))
      (node (ref "U$2") (pin "GND") (pinfunction "GND_GND") (pintype "power_in"))
      (node (ref "U$6") (pin "GND1") (pinfunction "GND1_GND1") (pintype "input"))
      (node (ref "X4") (pin "5") (pinfunction "5_5") (pintype "passive"))
    )
    (net (code "42") (name "Net-(CFG-Pad4)") (class "Default")
      (node (ref "CFG") (pin "4") (pinfunction "4_4") (pintype "passive"))
      (node (ref "U$3") (pin "CFG") (pinfunction "CFG_CFG") (pintype "bidirectional"))
    )
    (net (code "43") (name "Net-(I/O1-2)") (class "Default")
      (node (ref "I/O1") (pin "PWM") (pinfunction "2_PWM") (pintype "bidirectional"))
      (node (ref "LED2") (pin "C") (pinfunction "C_C") (pintype "passive"))
      (node (ref "Q1") (pin "2") (pinfunction "D_2") (pintype "passive"))
    )
    (net (code "44") (name "Net-(I/O1-3)") (class "Default")
      (node (ref "I/O1") (pin "I/O") (pinfunction "3_I/O") (pintype "bidirectional"))
      (node (ref "R") (pin "2") (pinfunction "2_2") (pintype "passive"))
    )
    (net (code "45") (name "Net-(I/O2-2)") (class "Default")
      (node (ref "I/O2") (pin "PWM") (pinfunction "2_PWM") (pintype "bidirectional"))
      (node (ref "LED5") (pin "C") (pinfunction "C_C") (pintype "passive"))
      (node (ref "Q2") (pin "2") (pinfunction "D_2") (pintype "passive"))
    )
    (net (code "46") (name "Net-(I/O2-3)") (class "Default")
      (node (ref "I/O2") (pin "I/O") (pinfunction "3_I/O") (pintype "bidirectional"))
      (node (ref "R32") (pin "2") (pinfunction "2_2") (pintype "passive"))
    )
    (net (code "47") (name "Net-(I/O3-2)") (class "Default")
      (node (ref "I/O3") (pin "PWM") (pinfunction "2_PWM") (pintype "bidirectional"))
      (node (ref "LED6") (pin "C") (pinfunction "C_C") (pintype "passive"))
      (node (ref "Q4") (pin "2") (pinfunction "D_2") (pintype "passive"))
    )
    (net (code "48") (name "Net-(I/O3-3)") (class "Default")
      (node (ref "I/O3") (pin "I/O") (pinfunction "3_I/O") (pintype "bidirectional"))
      (node (ref "R33") (pin "2") (pinfunction "2_2") (pintype "passive"))
    )
    (net (code "49") (name "Net-(I/O4-2)") (class "Default")
      (node (ref "I/O4") (pin "PWM") (pinfunction "2_PWM") (pintype "bidirectional"))
      (node (ref "LED7") (pin "C") (pinfunction "C_C") (pintype "passive"))
      (node (ref "Q5") (pin "2") (pinfunction "D_2") (pintype "passive"))
    )
    (net (code "50") (name "Net-(I/O4-3)") (class "Default")
      (node (ref "I/O4") (pin "I/O") (pinfunction "3_I/O") (pintype "bidirectional"))
      (node (ref "R34") (pin "2") (pinfunction "2_2") (pintype "passive"))
    )
    (net (code "51") (name "Net-(I/O5-2)") (class "Default")
      (node (ref "I/O5") (pin "PWM") (pinfunction "2_PWM") (pintype "bidirectional"))
      (node (ref "LED8") (pin "C") (pinfunction "C_C") (pintype "passive"))
      (node (ref "Q6") (pin "2") (pinfunction "D_2") (pintype "passive"))
    )
    (net (code "52") (name "Net-(I/O5-3)") (class "Default")
      (node (ref "I/O5") (pin "I/O") (pinfunction "3_I/O") (pintype "bidirectional"))
      (node (ref "R35") (pin "2") (pinfunction "2_2") (pintype "passive"))
    )
    (net (code "53") (name "Net-(IC2-+)") (class "Default")
      (node (ref "C13") (pin "1") (pinfunction "1_1") (pintype "passive"))
      (node (ref "C14") (pin "2") (pinfunction "2_2") (pintype "passive"))
      (node (ref "IC2") (pin "3") (pinfunction "+_3") (pintype "input"))
      (node (ref "R19") (pin "1") (pinfunction "1_1") (pintype "passive"))
    )
    (net (code "54") (name "Net-(IC2--)") (class "Default")
      (node (ref "C13") (pin "2") (pinfunction "2_2") (pintype "passive"))
      (node (ref "C15") (pin "1") (pinfunction "1_1") (pintype "passive"))
      (node (ref "IC2") (pin "2") (pinfunction "-_2") (pintype "input"))
      (node (ref "R20") (pin "1") (pinfunction "1_1") (pintype "passive"))
    )
    (net (code "55") (name "Net-(IC2-OUT)") (class "Default")
      (node (ref "IC2") (pin "6") (pinfunction "OUT_6") (pintype "output"))
      (node (ref "R9") (pin "1") (pinfunction "1_1") (pintype "passive"))
    )
    (net (code "56") (name "Net-(IC2-RG-Pad1)") (class "Default")
      (node (ref "IC2") (pin "1") (pinfunction "RG_1") (pintype "passive"))
      (node (ref "R2") (pin "2") (pinfunction "2_2") (pintype "passive"))
    )
    (net (code "57") (name "Net-(IC2-RG-Pad8)") (class "Default")
      (node (ref "IC2") (pin "8") (pinfunction "RG_8") (pintype "passive"))
      (node (ref "R2") (pin "1") (pinfunction "1_1") (pintype "passive"))
    )
    (net (code "58") (name "Net-(J7B-S)") (class "Default")
      (node (ref "J7") (pin "2") (pinfunction "S_2") (pintype "passive"))
      (node (ref "Q7") (pin "2") (pinfunction "D_2") (pintype "passive"))
    )
    (net (code "59") (name "Net-(LED1-PadA)") (class "Default")
      (node (ref "LED1") (pin "A") (pinfunction "A_A") (pintype "passive"))
      (node (ref "RL5") (pin "2") (pinfunction "2_2") (pintype "passive"))
    )
    (net (code "60") (name "Net-(LED2-PadA)") (class "Default")
      (node (ref "LED2") (pin "A") (pinfunction "A_A") (pintype "passive"))
      (node (ref "R25") (pin "1") (pinfunction "1_1") (pintype "passive"))
    )
    (net (code "61") (name "Net-(LED3-PadA)") (class "Default")
      (node (ref "LED3") (pin "A") (pinfunction "A_A") (pintype "passive"))
      (node (ref "R27") (pin "1") (pinfunction "1_1") (pintype "passive"))
    )
    (net (code "62") (name "Net-(LED4-PadA)") (class "Default")
      (node (ref "LED4") (pin "A") (pinfunction "A_A") (pintype "passive"))
      (node (ref "RL4") (pin "2") (pinfunction "2_2") (pintype "passive"))
    )
    (net (code "63") (name "Net-(LED5-PadA)") (class "Default")
      (node (ref "LED5") (pin "A") (pinfunction "A_A") (pintype "passive"))
      (node (ref "R4") (pin "1") (pinfunction "1_1") (pintype "passive"))
    )
    (net (code "64") (name "Net-(LED6-PadA)") (class "Default")
      (node (ref "LED6") (pin "A") (pinfunction "A_A") (pintype "passive"))
      (node (ref "R5") (pin "1") (pinfunction "1_1") (pintype "passive"))
    )
    (net (code "65") (name "Net-(LED7-PadA)") (class "Default")
      (node (ref "LED7") (pin "A") (pinfunction "A_A") (pintype "passive"))
      (node (ref "R6") (pin "1") (pinfunction "1_1") (pintype "passive"))
    )
    (net (code "66") (name "Net-(LED8-PadA)") (class "Default")
      (node (ref "LED8") (pin "A") (pinfunction "A_A") (pintype "passive"))
      (node (ref "R7") (pin "1") (pinfunction "1_1") (pintype "passive"))
    )
    (net (code "67") (name "Net-(LED9-PadA)") (class "Default")
      (node (ref "LED9") (pin "A") (pinfunction "A_A") (pintype "passive"))
      (node (ref "R12") (pin "1") (pinfunction "1_1") (pintype "passive"))
    )
    (net (code "68") (name "Net-(LED10-PadA)") (class "Default")
      (node (ref "LED10") (pin "A") (pinfunction "A_A") (pintype "passive"))
      (node (ref "RL3") (pin "1") (pinfunction "1_1") (pintype "passive"))
    )
    (net (code "69") (name "Net-(LED11-PadA)") (class "Default")
      (node (ref "LED11") (pin "A") (pinfunction "A_A") (pintype "passive"))
      (node (ref "R14") (pin "1") (pinfunction "1_1") (pintype "passive"))
    )
    (net (code "70") (name "Net-(LED11-PadC)") (class "Default")
      (node (ref "LED11") (pin "C") (pinfunction "C_C") (pintype "passive"))
      (node (ref "U$3") (pin "NET") (pinfunction "NET_NET") (pintype "bidirectional"))
    )
    (net (code "71") (name "Net-(LED12-PadA)") (class "Default")
      (node (ref "LED12") (pin "A") (pinfunction "A_A") (pintype "passive"))
      (node (ref "R39") (pin "1") (pinfunction "1_1") (pintype "passive"))
    )
    (net (code "72") (name "Net-(LED12-PadC)") (class "Default")
      (node (ref "LED12") (pin "C") (pinfunction "C_C") (pintype "passive"))
      (node (ref "U$3") (pin "ALM") (pinfunction "ALM_ALM") (pintype "bidirectional"))
    )
    (net (code "73") (name "Net-(Q7-G)") (class "Default")
      (node (ref "Q7") (pin "1") (pinfunction "G_1") (pintype "passive"))
      (node (ref "RL2") (pin "2") (pinfunction "2_2") (pintype "passive"))
    )
    (net (code "74") (name "Net-(R8-Pad2)") (class "Default")
      (node (ref "R8") (pin "2") (pinfunction "2_2") (pintype "passive"))
      (node (ref "U$3") (pin "TX1") (pinfunction "TX1_TX1") (pintype "bidirectional"))
    )
    (net (code "75") (name "Net-(R11-Pad2)") (class "Default")
      (node (ref "R11") (pin "2") (pinfunction "2_2") (pintype "passive"))
      (node (ref "U$3") (pin "RX1") (pinfunction "RX1_RX1") (pintype "bidirectional"))
    )
    (net (code "76") (name "Net-(R18-Pad2)") (class "Default")
      (node (ref "R18") (pin "2") (pinfunction "2_2") (pintype "passive"))
      (node (ref "U$1") (pin "SCK") (pinfunction "SCK_SCK") (pintype "bidirectional"))
    )
    (net (code "77") (name "Net-(R24-Pad2)") (class "Default")
      (node (ref "R24") (pin "2") (pinfunction "2_2") (pintype "passive"))
      (node (ref "X4") (pin "3") (pinfunction "3_3") (pintype "passive"))
    )
    (net (code "78") (name "Net-(R31-Pad2)") (class "Default")
      (node (ref "R31") (pin "2") (pinfunction "2_2") (pintype "passive"))
      (node (ref "X4") (pin "2") (pinfunction "2_2") (pintype "passive"))
    )
    (net (code "79") (name "Net-(U$1-CS)") (class "Default")
      (node (ref "R16") (pin "1") (pinfunction "1_1") (pintype "passive"))
      (node (ref "R17") (pin "1") (pinfunction "1_1") (pintype "passive"))
      (node (ref "U$1") (pin "CE") (pinfunction "CS_CE") (pintype "bidirectional"))
    )
    (net (code "80") (name "Net-(U$3-RNU)") (class "Default")
      (node (ref "LED9") (pin "C") (pinfunction "C_C") (pintype "passive"))
      (node (ref "U$3") (pin "RUN") (pinfunction "RNU_RUN") (pintype "bidirectional"))
    )
    (net (code "81") (name "Net-(U$4-AVCC)") (class "Default")
      (node (ref "C16") (pin "2") (pinfunction "2_2") (pintype "passive"))
      (node (ref "L1") (pin "1") (pinfunction "1_1") (pintype "passive"))
      (node (ref "U$4") (pin "24") (pinfunction "AVCC_24") (pintype "bidirectional"))
    )
    (net (code "82") (name "Net-(U$4-UCAP)") (class "Default")
      (node (ref "C3") (pin "2") (pinfunction "2_2") (pintype "passive"))
      (node (ref "U$4") (pin "6") (pinfunction "UCAP_6") (pintype "bidirectional"))
    )
    (net (code "83") (name "Net-(X1B-S)") (class "Default")
      (node (ref "R20") (pin "2") (pinfunction "2_2") (pintype "passive"))
      (node (ref "X1") (pin "2") (pinfunction "S_2") (pintype "passive"))
    )
    (net (code "84") (name "Net-(X1C-S)") (class "Default")
      (node (ref "R19") (pin "2") (pinfunction "2_2") (pintype "passive"))
      (node (ref "X1") (pin "3") (pinfunction "S_3") (pintype "passive"))
    )
    (net (code "85") (name "Net-(X2B-S)") (class "Default")
      (node (ref "R10") (pin "2") (pinfunction "2_2") (pintype "passive"))
      (node (ref "RL6") (pin "2") (pinfunction "2_2") (pintype "passive"))
      (node (ref "X2") (pin "2") (pinfunction "S_2") (pintype "passive"))
    )
    (net (code "86") (name "Net-(X5B-S)") (class "Default")
      (node (ref "R21") (pin "2") (pinfunction "2_2") (pintype "passive"))
      (node (ref "RL8") (pin "2") (pinfunction "2_2") (pintype "passive"))
      (node (ref "X5") (pin "2") (pinfunction "S_2") (pintype "passive"))
    )
    (net (code "87") (name "VUSB") (class "Default")
      (node (ref "C7") (pin "2") (pinfunction "2_2") (pintype "passive"))
      (node (ref "D4") (pin "A") (pinfunction "A_A") (pintype "passive"))
      (node (ref "U$4") (pin "7") (pinfunction "VBUS_7") (pintype "bidirectional"))
      (node (ref "X4") (pin "1") (pinfunction "1_1") (pintype "passive"))
    )
    (net (code "88") (name "unconnected-(CFG-Pad2)") (class "Default")
      (node (ref "CFG") (pin "2") (pinfunction "2_2") (pintype "passive"))
    )
    (net (code "89") (name "unconnected-(CFG-Pad3)") (class "Default")
      (node (ref "CFG") (pin "3") (pinfunction "3_3") (pintype "passive"))
    )
    (net (code "90") (name "unconnected-(Q1-D-Pad4)") (class "Default")
      (node (ref "Q1") (pin "4") (pinfunction "D_4") (pintype "passive"))
    )
    (net (code "91") (name "unconnected-(Q2-D-Pad4)") (class "Default")
      (node (ref "Q2") (pin "4") (pinfunction "D_4") (pintype "passive"))
    )
    (net (code "92") (name "unconnected-(Q4-D-Pad4)") (class "Default")
      (node (ref "Q4") (pin "4") (pinfunction "D_4") (pintype "passive"))
    )
    (net (code "93") (name "unconnected-(Q5-D-Pad4)") (class "Default")
      (node (ref "Q5") (pin "4") (pinfunction "D_4") (pintype "passive"))
    )
    (net (code "94") (name "unconnected-(Q6-D-Pad4)") (class "Default")
      (node (ref "Q6") (pin "4") (pinfunction "D_4") (pintype "passive"))
    )
    (net (code "95") (name "unconnected-(RESET1-Pad1)") (class "Default")
      (node (ref "RESET1") (pin "1") (pinfunction "1_1") (pintype "passive"))
    )
    (net (code "96") (name "unconnected-(RESET1-Pad3)") (class "Default")
      (node (ref "RESET1") (pin "3") (pinfunction "3_3") (pintype "passive"))
    )
    (net (code "97") (name "unconnected-(U$3-PadRST)") (class "Default")
      (node (ref "U$3") (pin "RST") (pinfunction "RST_RST") (pintype "bidirectional"))
    )
    (net (code "98") (name "unconnected-(X4-Pad4)") (class "Default")
      (node (ref "X4") (pin "4") (pinfunction "4_4") (pintype "passive"))
    )
  )
)
